# Mainboard_V1_0_Sensors.net
KiCad netlist of a schematic drawn in Altium Designer
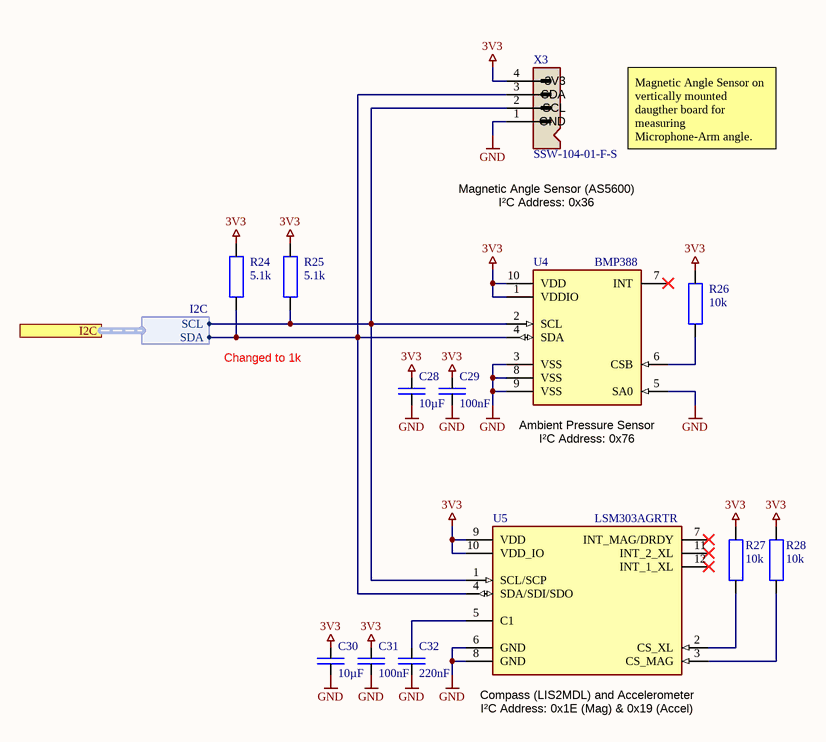
[diagram p0: Mainboard_V1.0_Sensors.SchDoc]

(export (version "E")
  (design (tool "Eeschema 10.0.6"))
  (components
    (comp (ref "C28")
      (value "10µF")
      (footprint "SMD Keramikkondensator 1206")
      (description "SMD Ceramic Capacitor E6")
      (libsource (lib "Ceramic Capacitors-E6") (part "E6 - 10uF"))
    )
    (comp (ref "C29")
      (value "100nF")
      (footprint "SMD Keramikkondensator 0603")
      (description "SMD Ceramic Capacitor E6")
      (libsource (lib "Ceramic Capacitors-E6") (part "E6 - 100nF"))
    )
    (comp (ref "C30")
      (value "10µF")
      (footprint "SMD Keramikkondensator 1206")
      (description "SMD Ceramic Capacitor E6")
      (libsource (lib "Ceramic Capacitors-E6") (part "E6 - 10uF"))
    )
    (comp (ref "C31")
      (value "100nF")
      (footprint "SMD Keramikkondensator 0603")
      (description "SMD Ceramic Capacitor E6")
      (libsource (lib "Ceramic Capacitors-E6") (part "E6 - 100nF"))
    )
    (comp (ref "C32")
      (value "220nF")
      (footprint "SMD Keramikkondensator 0603")
      (description "SMD Ceramic Capacitor E6")
      (libsource (lib "Ceramic Capacitors-E6") (part "E6 - 100nF"))
    )
    (comp (ref "R24")
      (value "5.1k")
      (footprint "SMD Widerstand 0603")
      (description "RES (E=Heizwiderstand B=Messwandler)")
      (libsource (lib "") (part "R-RESISTOR_1"))
    )
    (comp (ref "R25")
      (value "5.1k")
      (footprint "SMD Widerstand 0603")
      (description "RES (E=Heizwiderstand B=Messwandler)")
      (libsource (lib "") (part "R-RESISTOR_1"))
    )
    (comp (ref "R26")
      (value "10k")
      (footprint "SMD Widerstand 0603")
      (description "RES (E=Heizwiderstand B=Messwandler)")
      (libsource (lib "TFS Integrated Library") (part "R-RESISTOR"))
    )
    (comp (ref "R27")
      (value "10k")
      (footprint "SMD Widerstand 0603")
      (description "RES (E=Heizwiderstand B=Messwandler)")
      (libsource (lib "TFS Integrated Library") (part "R-RESISTOR"))
    )
    (comp (ref "R28")
      (value "10k")
      (footprint "SMD Widerstand 0603")
      (description "RES (E=Heizwiderstand B=Messwandler)")
      (libsource (lib "TFS Integrated Library") (part "R-RESISTOR"))
    )
    (comp (ref "U4")
      (value "BMP388")
      (footprint "SMD IC LGA-10")
      (description "Digital Pressure Sensor")
      (libsource (lib "Mainboard") (part "U-BMP388"))
    )
    (comp (ref "U5")
      (value "LSM303AGRTR")
      (footprint "SMD IC LGA-12")
      (description "High-Performance eCompass Module")
      (libsource (lib "Mainboard") (part "U-LSM303AGRTR"))
    )
    (comp (ref "X3")
      (value "SSW-104-01-F-S")
      (footprint "THT Buchsenleiste 4-Pol (1x4)")
      (libsource (lib "Audio-Beamformer") (part "X-Stiftleiste (4-Fach)"))
    )
  )
  (nets
    (net (code "3") (name "3V3") (class "Default")
      (node (ref "C28") (pin "2") (pinfunction "2_2") (pintype "passive"))
      (node (ref "C29") (pin "2") (pinfunction "2_2") (pintype "passive"))
      (node (ref "C30") (pin "2") (pinfunction "2_2") (pintype "passive"))
      (node (ref "C31") (pin "2") (pinfunction "2_2") (pintype "passive"))
      (node (ref "R24") (pin "1") (pinfunction "1_1") (pintype "passive"))
      (node (ref "R25") (pin "1") (pinfunction "1_1") (pintype "passive"))
      (node (ref "R26") (pin "2") (pinfunction "2_2") (pintype "passive"))
      (node (ref "R27") (pin "2") (pinfunction "2_2") (pintype "passive"))
      (node (ref "R28") (pin "2") (pinfunction "2_2") (pintype "passive"))
      (node (ref "U4") (pin "1") (pinfunction "VDDIO_1") (pintype "power_in"))
      (node (ref "U4") (pin "10") (pinfunction "VDD_10") (pintype "power_in"))
      (node (ref "U5") (pin "10") (pinfunction "VDD_IO_10") (pintype "power_in"))
      (node (ref "U5") (pin "9") (pinfunction "VDD_9") (pintype "power_in"))
      (node (ref "X3") (pin "4") (pinfunction "4_4") (pintype "passive"))
    )
    (net (code "4") (name "GND") (class "Default")
      (node (ref "C28") (pin "1") (pinfunction "1_1") (pintype "passive"))
      (node (ref "C29") (pin "1") (pinfunction "1_1") (pintype "passive"))
      (node (ref "C30") (pin "1") (pinfunction "1_1") (pintype "passive"))
      (node (ref "C31") (pin "1") (pinfunction "1_1") (pintype "passive"))
      (node (ref "C32") (pin "1") (pinfunction "1_1") (pintype "passive"))
      (node (ref "U4") (pin "3") (pinfunction "VSS_3") (pintype "power_in"))
      (node (ref "U4") (pin "5") (pinfunction "SA0_5") (pintype "input"))
      (node (ref "U4") (pin "8") (pinfunction "VSS_8") (pintype "power_in"))
      (node (ref "U4") (pin "9") (pinfunction "VSS_9") (pintype "power_in"))
      (node (ref "U5") (pin "6") (pinfunction "GND_6") (pintype "power_in"))
      (node (ref "U5") (pin "8") (pinfunction "GND_8") (pintype "power_in"))
      (node (ref "X3") (pin "1") (pinfunction "1_1") (pintype "passive"))
    )
    (net (code "5") (name "Net-(U4-CSB)") (class "Default")
      (node (ref "R26") (pin "1") (pinfunction "1_1") (pintype "passive"))
      (node (ref "U4") (pin "6") (pinfunction "CSB_6") (pintype "input"))
    )
    (net (code "6") (name "Net-(U4-SCL)") (class "Default")
      (node (ref "R25") (pin "2") (pinfunction "2_2") (pintype "passive"))
      (node (ref "U4") (pin "2") (pinfunction "SCL_2") (pintype "input"))
      (node (ref "U5") (pin "1") (pinfunction "SCL/SCP_1") (pintype "input"))
      (node (ref "X3") (pin "2") (pinfunction "2_2") (pintype "passive"))
    )
    (net (code "7") (name "Net-(U4-SDA)") (class "Default")
      (node (ref "R24") (pin "2") (pinfunction "2_2") (pintype "passive"))
      (node (ref "U4") (pin "4") (pinfunction "SDA_4") (pintype "bidirectional"))
      (node (ref "U5") (pin "4") (pinfunction "SDA/SDI/SDO_4") (pintype "bidirectional"))
      (node (ref "X3") (pin "3") (pinfunction "3_3") (pintype "passive"))
    )
    (net (code "8") (name "Net-(U5-C1)") (class "Default")
      (node (ref "C32") (pin "2") (pinfunction "2_2") (pintype "passive"))
      (node (ref "U5") (pin "5") (pinfunction "C1_5") (pintype "passive"))
    )
    (net (code "9") (name "Net-(U5-CS_MAG)") (class "Default")
      (node (ref "R28") (pin "1") (pinfunction "1_1") (pintype "passive"))
      (node (ref "U5") (pin "3") (pinfunction "CS_MAG_3") (pintype "input"))
    )
    (net (code "10") (name "Net-(U5-CS_XL)") (class "Default")
      (node (ref "R27") (pin "1") (pinfunction "1_1") (pintype "passive"))
      (node (ref "U5") (pin "2") (pinfunction "CS_XL_2") (pintype "input"))
    )
    (net (code "11") (name "unconnected-(U4-INT-Pad7)") (class "Default")
      (node (ref "U4") (pin "7") (pinfunction "INT_7") (pintype "open_collector+no_connect"))
    )
    (net (code "12") (name "unconnected-(U5-INT_1_XL-Pad12)") (class "Default")
      (node (ref "U5") (pin "12") (pinfunction "INT_1_XL_12") (pintype "open_collector+no_connect"))
    )
    (net (code "13") (name "unconnected-(U5-INT_2_XL-Pad11)") (class "Default")
      (node (ref "U5") (pin "11") (pinfunction "INT_2_XL_11") (pintype "open_collector+no_connect"))
    )
    (net (code "14") (name "unconnected-(U5-INT_MAG{slash}DRDY-Pad7)") (class "Default")
      (node (ref "U5") (pin "7") (pinfunction "INT_MAG/DRDY_7") (pintype "open_collector+no_connect"))
    )
  )
)
